# SparkFun_Main_Board_Single_v20.net
KiCad netlist of a schematic drawn in EAGLE
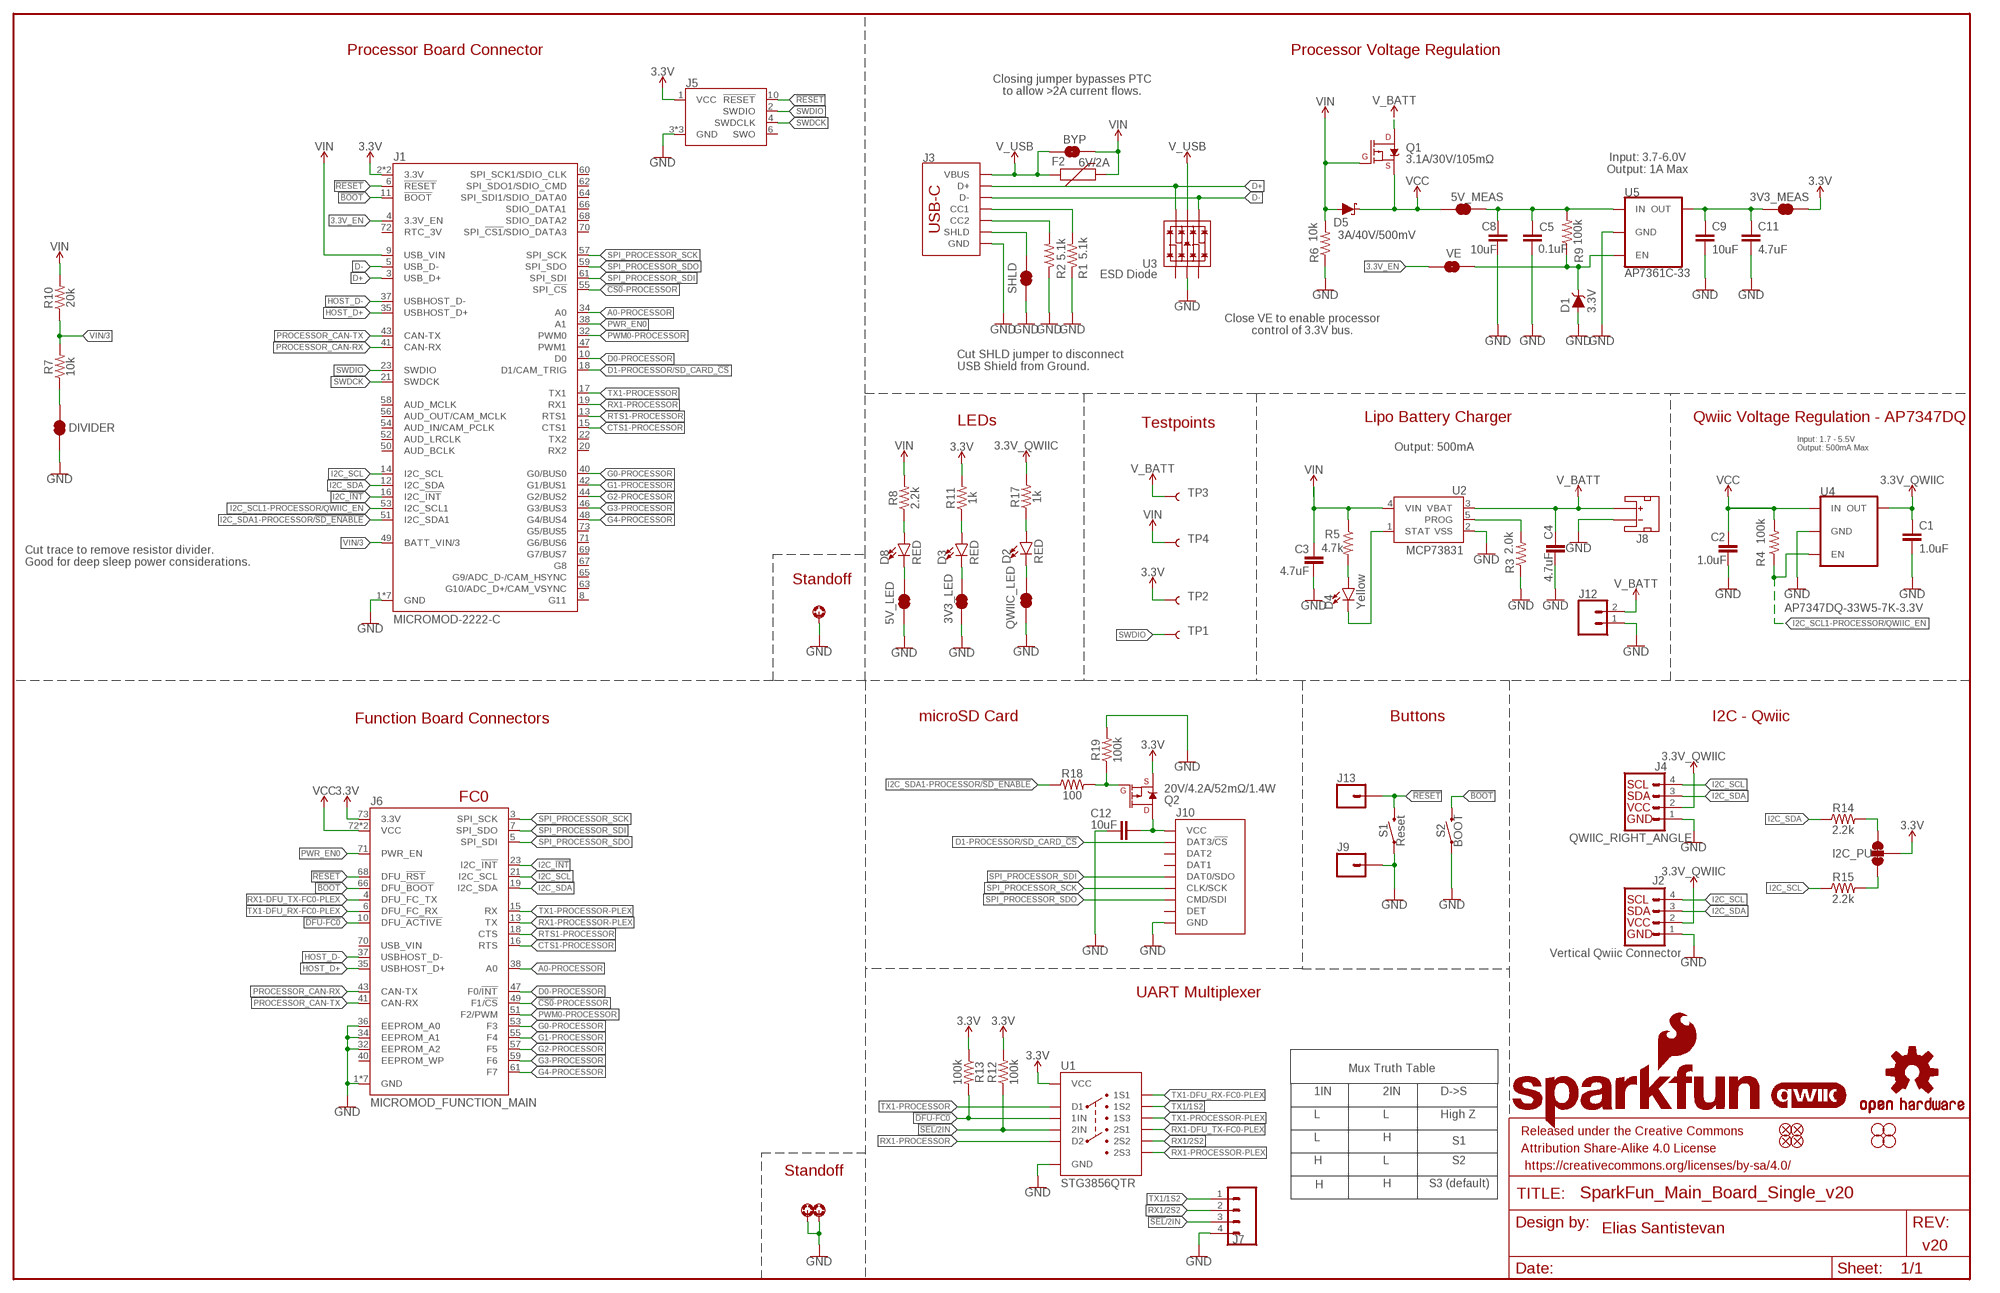
[diagram p0: schematic, sheet 1]

(export (version "E")
  (design (tool "Eeschema 10.0.6"))
  (components
    (comp (ref "3V3_LED")
      (value "JUMPER-SMT_2_NC_TRACE_SILK")
      (footprint "eagle-import:SMT-JUMPER_2_NC_TRACE_SILK")
      (libsource (lib "eagle-import") (part "JUMPER-SMT_2_NC_TRACE_SILK"))
    )
    (comp (ref "3V3_MEAS")
      (value "JUMPER-COMBO_2_NC_TRACE")
      (footprint "eagle-import:COMBO-JUMPER_2_NC_TRACE")
      (libsource (lib "eagle-import") (part "JUMPER-COMBO_2_NC_TRACE"))
    )
    (comp (ref "5V_LED")
      (value "JUMPER-SMT_2_NC_TRACE_SILK")
      (footprint "eagle-import:SMT-JUMPER_2_NC_TRACE_SILK")
      (libsource (lib "eagle-import") (part "JUMPER-SMT_2_NC_TRACE_SILK"))
    )
    (comp (ref "5V_MEAS")
      (value "JUMPER-COMBO_2_NC_TRACE")
      (footprint "eagle-import:COMBO-JUMPER_2_NC_TRACE")
      (libsource (lib "eagle-import") (part "JUMPER-COMBO_2_NC_TRACE"))
    )
    (comp (ref "BYP")
      (value "JUMPER-SMT_2_NO_SILK")
      (footprint "eagle-import:SMT-JUMPER_2_NO_SILK")
      (libsource (lib "eagle-import") (part "JUMPER-SMT_2_NO_SILK"))
    )
    (comp (ref "C1")
      (value "1.0uF")
      (footprint "eagle-import:0603")
      (libsource (lib "eagle-import") (part "1.0UF-0603-16V-10%"))
    )
    (comp (ref "C2")
      (value "1.0uF")
      (footprint "eagle-import:0603")
      (libsource (lib "eagle-import") (part "1.0UF-0603-16V-10%"))
    )
    (comp (ref "C3")
      (value "4.7uF")
      (footprint "eagle-import:0603")
      (libsource (lib "eagle-import") (part "4.7UF-0603-6.3V-(10%)"))
    )
    (comp (ref "C4")
      (value "4.7uF")
      (footprint "eagle-import:0603")
      (libsource (lib "eagle-import") (part "4.7UF-0603-35V-(20%)"))
    )
    (comp (ref "C5")
      (value "0.1uF")
      (footprint "eagle-import:0603")
      (libsource (lib "eagle-import") (part "0.1UF-0603-25V-(+80/-20%)"))
    )
    (comp (ref "C8")
      (value "10uF")
      (footprint "eagle-import:0805")
      (libsource (lib "eagle-import") (part "10UF-0805-10V-10%"))
    )
    (comp (ref "C9")
      (value "10uF")
      (footprint "eagle-import:0603")
      (libsource (lib "eagle-import") (part "10UF-0603-6.3V-20%"))
    )
    (comp (ref "C11")
      (value "4.7uF")
      (footprint "eagle-import:0603")
      (libsource (lib "eagle-import") (part "4.7UF-0603-6.3V-(10%)"))
    )
    (comp (ref "C12")
      (value "10uF")
      (footprint "eagle-import:0603")
      (libsource (lib "eagle-import") (part "10UF-0603-6.3V-20%"))
    )
    (comp (ref "D1")
      (value "3.3V")
      (footprint "eagle-import:SOD-323")
      (libsource (lib "eagle-import") (part "DIODE-ZENER-MM3Z3V3T1G"))
    )
    (comp (ref "D2")
      (value "RED")
      (footprint "eagle-import:LED-0603")
      (libsource (lib "eagle-import") (part "LED-RED0603"))
    )
    (comp (ref "D3")
      (value "RED")
      (footprint "eagle-import:LED-0603")
      (libsource (lib "eagle-import") (part "LED-RED0603"))
    )
    (comp (ref "D4")
      (value "Yellow")
      (footprint "eagle-import:LED-0603")
      (libsource (lib "eagle-import") (part "LED-YELLOW0603"))
    )
    (comp (ref "D5")
      (value "3A/40V/500mV")
      (footprint "eagle-import:SMA-DIODE")
      (libsource (lib "eagle-import") (part "DIODE-SCHOTTKY-B340A"))
    )
    (comp (ref "D8")
      (value "RED")
      (footprint "eagle-import:LED-0603")
      (libsource (lib "eagle-import") (part "LED-RED0603"))
    )
    (comp (ref "DIVIDER")
      (value "JUMPER-SMT_2_NC_TRACE_SILK")
      (footprint "eagle-import:SMT-JUMPER_2_NC_TRACE_SILK")
      (libsource (lib "eagle-import") (part "JUMPER-SMT_2_NC_TRACE_SILK"))
    )
    (comp (ref "F2")
      (value "6V/2A")
      (footprint "eagle-import:1210")
      (libsource (lib "eagle-import") (part "PPTC_6V2A"))
    )
    (comp (ref "FD1")
      (value "FIDUCIAL1X2")
      (footprint "eagle-import:FIDUCIAL-1X2")
      (libsource (lib "eagle-import") (part "FIDUCIAL1X2"))
    )
    (comp (ref "FD2")
      (value "FIDUCIAL1X2")
      (footprint "eagle-import:FIDUCIAL-1X2")
      (libsource (lib "eagle-import") (part "FIDUCIAL1X2"))
    )
    (comp (ref "FD3")
      (value "FIDUCIAL1X2")
      (footprint "eagle-import:FIDUCIAL-1X2")
      (libsource (lib "eagle-import") (part "FIDUCIAL1X2"))
    )
    (comp (ref "FD4")
      (value "FIDUCIAL1X2")
      (footprint "eagle-import:FIDUCIAL-1X2")
      (libsource (lib "eagle-import") (part "FIDUCIAL1X2"))
    )
    (comp (ref "FRAME1")
      (value "FRAME-LEDGER")
      (footprint "eagle-import:CREATIVE_COMMONS")
      (libsource (lib "eagle-import") (part "FRAME-LEDGER"))
    )
    (comp (ref "H2")
      (value "STAND-OFF-REFLOW-M2.5_2.5MM_TALL")
      (footprint "eagle-import:STAND-OFF-REFLOW-M2.5")
      (libsource (lib "eagle-import") (part "STAND-OFF-REFLOW-M2.5_2.5MM_TALL"))
    )
    (comp (ref "H4")
      (value "STAND-OFF-REFLOW-M2.5_2.5MM_TALL")
      (footprint "eagle-import:STAND-OFF-REFLOW-M2.5")
      (libsource (lib "eagle-import") (part "STAND-OFF-REFLOW-M2.5_2.5MM_TALL"))
    )
    (comp (ref "H8")
      (value "STAND-OFF-REFLOW-M2.5_2.5MM_TALL")
      (footprint "eagle-import:STAND-OFF-REFLOW-M2.5")
      (libsource (lib "eagle-import") (part "STAND-OFF-REFLOW-M2.5_2.5MM_TALL"))
    )
    (comp (ref "H14")
      (value "STAND-OFFTIGHT")
      (footprint "eagle-import:STAND-OFF-TIGHT")
      (libsource (lib "eagle-import") (part "STAND-OFFTIGHT"))
    )
    (comp (ref "H15")
      (value "STAND-OFFTIGHT")
      (footprint "eagle-import:STAND-OFF-TIGHT")
      (libsource (lib "eagle-import") (part "STAND-OFFTIGHT"))
    )
    (comp (ref "H16")
      (value "STAND-OFFTIGHT")
      (footprint "eagle-import:STAND-OFF-TIGHT")
      (libsource (lib "eagle-import") (part "STAND-OFFTIGHT"))
    )
    (comp (ref "H17")
      (value "STAND-OFFTIGHT")
      (footprint "eagle-import:STAND-OFF-TIGHT")
      (libsource (lib "eagle-import") (part "STAND-OFFTIGHT"))
    )
    (comp (ref "I2C_PU")
      (value "JUMPER-SMT_3_2-NC_TRACE_SILK")
      (footprint "eagle-import:SMT-JUMPER_3_2-NC_TRACE_SILK")
      (libsource (lib "eagle-import") (part "JUMPER-SMT_3_2-NC_TRACE_SILK"))
    )
    (comp (ref "J1")
      (value "MICROMOD-2222-C")
      (footprint "eagle-import:M.2-CONNECTOR-E")
      (libsource (lib "eagle-import") (part "MICROMOD-2222-C"))
    )
    (comp (ref "J2")
      (value "Vertical Qwiic Connector")
      (footprint "eagle-import:JST04_1MM_VERT")
      (libsource (lib "eagle-import") (part "QWIIC_CONNECTOR"))
    )
    (comp (ref "J3")
      (value "USB_C_2-LAYER_PADS")
      (footprint "eagle-import:USB-C-16P-2LAYER-PADS")
      (libsource (lib "eagle-import") (part "USB_C_2-LAYER_PADS"))
    )
    (comp (ref "J4")
      (value "QWIIC_RIGHT_ANGLE")
      (footprint "eagle-import:JST04_1MM_RA")
      (libsource (lib "eagle-import") (part "QWIIC_CONNECTORJS-1MM"))
    )
    (comp (ref "J5")
      (value "CORTEX_JTAG_DEBUG_MINIMUM_PTH")
      (footprint "eagle-import:2X5-PTH-1.27MM")
      (libsource (lib "eagle-import") (part "CORTEX_JTAG_DEBUG_MINIMUM_PTH"))
    )
    (comp (ref "J6")
      (value "MICROMOD_FUNCTION_MAIN")
      (footprint "eagle-import:M.2-CONNECTOR-E-FUNCTION-STANDARD")
      (libsource (lib "eagle-import") (part "MICROMOD_FUNCTION_MAIN"))
    )
    (comp (ref "J7")
      (value "CONN_041X04_NO_SILK")
      (footprint "eagle-import:1X04_NO_SILK")
      (libsource (lib "eagle-import") (part "CONN_041X04_NO_SILK"))
    )
    (comp (ref "J8")
      (value "JST_2MM_MALE")
      (footprint "eagle-import:JST-2-SMD")
      (libsource (lib "eagle-import") (part "JST_2MM_MALE"))
    )
    (comp (ref "J9")
      (value "CONN_01PTH_NO_SILK_YES_STOP")
      (footprint "eagle-import:1X01_NO_SILK")
      (libsource (lib "eagle-import") (part "CONN_01PTH_NO_SILK_YES_STOP"))
    )
    (comp (ref "J10")
      (value "MICRO-SD-PUSH-PUSH-EXT-PIN")
      (footprint "eagle-import:MICROSD-EXTERNALPIN")
      (libsource (lib "eagle-import") (part "MICRO-SD-PUSH-PUSH-EXT-PIN"))
    )
    (comp (ref "J12")
      (value "CONN_021X02_NO_SILK")
      (footprint "eagle-import:1X02_NO_SILK")
      (libsource (lib "eagle-import") (part "CONN_021X02_NO_SILK"))
    )
    (comp (ref "J13")
      (value "CONN_01PTH_NO_SILK_YES_STOP")
      (footprint "eagle-import:1X01_NO_SILK")
      (libsource (lib "eagle-import") (part "CONN_01PTH_NO_SILK_YES_STOP"))
    )
    (comp (ref "LOGO1")
      (value "QWIIC_LOGO_8MM")
      (footprint "eagle-import:QWIIC_8MM")
      (libsource (lib "eagle-import") (part "QWIIC_LOGO_8MM"))
    )
    (comp (ref "LOGO2")
      (value "SFE_LOGO_NAME_FLAME.3_INCH")
      (footprint "eagle-import:SFE_LOGO_NAME_FLAME_.3")
      (libsource (lib "eagle-import") (part "SFE_LOGO_NAME_FLAME.3_INCH"))
    )
    (comp (ref "LOGO3")
      (value "OSHW-LOGOL")
      (footprint "eagle-import:OSHW-LOGO-L")
      (libsource (lib "eagle-import") (part "OSHW-LOGOL"))
    )
    (comp (ref "Q1")
      (value "3.1A/30V/105mΩ")
      (footprint "eagle-import:SOT23-3")
      (libsource (lib "eagle-import") (part "MOSFET_PCH-DMG2307L"))
    )
    (comp (ref "Q2")
      (value "20V/4.2A/52mΩ/1.4W")
      (footprint "eagle-import:SOT23-3")
      (libsource (lib "eagle-import") (part "MOSFET_PCH-DMG2305UX-7"))
    )
    (comp (ref "QWIIC_LED")
      (value "JUMPER-SMT_2_NC_TRACE_SILK")
      (footprint "eagle-import:SMT-JUMPER_2_NC_TRACE_SILK")
      (libsource (lib "eagle-import") (part "JUMPER-SMT_2_NC_TRACE_SILK"))
    )
    (comp (ref "R1")
      (value "5.1k")
      (footprint "eagle-import:0603")
      (libsource (lib "eagle-import") (part "5.1KOHM5.1KOHM-0603-1/10W-1%"))
    )
    (comp (ref "R2")
      (value "5.1k")
      (footprint "eagle-import:0603")
      (libsource (lib "eagle-import") (part "5.1KOHM5.1KOHM-0603-1/10W-1%"))
    )
    (comp (ref "R3")
      (value "2.0k")
      (footprint "eagle-import:0603")
      (libsource (lib "eagle-import") (part "2.0KOHM-0603-1/10W-5%"))
    )
    (comp (ref "R4")
      (value "100k")
      (footprint "eagle-import:0603")
      (libsource (lib "eagle-import") (part "100KOHM-0603-1/10W-1%"))
    )
    (comp (ref "R5")
      (value "4.7k")
      (footprint "eagle-import:0603")
      (libsource (lib "eagle-import") (part "4.7KOHM-0603-1/10W-1%"))
    )
    (comp (ref "R6")
      (value "10k")
      (footprint "eagle-import:0603")
      (libsource (lib "eagle-import") (part "10KOHM-0603-1/10W-1%"))
    )
    (comp (ref "R7")
      (value "10k")
      (footprint "eagle-import:0603")
      (libsource (lib "eagle-import") (part "10KOHM-0603-1/10W-1%"))
    )
    (comp (ref "R8")
      (value "2.2k")
      (footprint "eagle-import:0603")
      (libsource (lib "eagle-import") (part "2.2KOHM-0603-1/10W-1%"))
    )
    (comp (ref "R9")
      (value "100k")
      (footprint "eagle-import:0603")
      (libsource (lib "eagle-import") (part "100KOHM-0603-1/10W-1%"))
    )
    (comp (ref "R10")
      (value "20k")
      (footprint "eagle-import:0603")
      (libsource (lib "eagle-import") (part "20KOHM-0603-1/10W-1%"))
    )
    (comp (ref "R11")
      (value "1k")
      (footprint "eagle-import:0603")
      (libsource (lib "eagle-import") (part "1KOHM-0603-1/10W-1%"))
    )
    (comp (ref "R12")
      (value "100k")
      (footprint "eagle-import:0603")
      (libsource (lib "eagle-import") (part "100KOHM-0603-1/10W-1%"))
    )
    (comp (ref "R13")
      (value "100k")
      (footprint "eagle-import:0603")
      (libsource (lib "eagle-import") (part "100KOHM-0603-1/10W-1%"))
    )
    (comp (ref "R14")
      (value "2.2k")
      (footprint "eagle-import:0603")
      (libsource (lib "eagle-import") (part "2.2KOHM-0603-1/10W-1%"))
    )
    (comp (ref "R15")
      (value "2.2k")
      (footprint "eagle-import:0603")
      (libsource (lib "eagle-import") (part "2.2KOHM-0603-1/10W-1%"))
    )
    (comp (ref "R17")
      (value "1k")
      (footprint "eagle-import:0603")
      (libsource (lib "eagle-import") (part "1KOHM-0603-1/10W-1%"))
    )
    (comp (ref "R18")
      (value "100")
      (footprint "eagle-import:0603")
      (libsource (lib "eagle-import") (part "100OHM-0603-1/10W-1%"))
    )
    (comp (ref "R19")
      (value "100k")
      (footprint "eagle-import:0603")
      (libsource (lib "eagle-import") (part "100KOHM-0603-1/10W-1%"))
    )
    (comp (ref "S1")
      (value "Reset")
      (footprint "eagle-import:TACTILE_SWITCH_SMD_5.2MM")
      (libsource (lib "eagle-import") (part "MOMENTARY-SWITCH-SPST-SMD-5.2-TALL-REDUNDANT"))
    )
    (comp (ref "S2")
      (value "BOOT")
      (footprint "eagle-import:TACTILE_SWITCH_SMD_5.2MM")
      (libsource (lib "eagle-import") (part "MOMENTARY-SWITCH-SPST-SMD-5.2-TALL-REDUNDANT"))
    )
    (comp (ref "SHLD")
      (value "JUMPER-SMT_2_NC_TRACE_SILK")
      (footprint "eagle-import:SMT-JUMPER_2_NC_TRACE_SILK")
      (libsource (lib "eagle-import") (part "JUMPER-SMT_2_NC_TRACE_SILK"))
    )
    (comp (ref "TP1")
      (value "TEST-POINT3X5")
      (footprint "eagle-import:PAD.03X.05")
      (libsource (lib "eagle-import") (part "TEST-POINT3X5"))
    )
    (comp (ref "TP2")
      (value "TEST-POINT3X5")
      (footprint "eagle-import:PAD.03X.05")
      (libsource (lib "eagle-import") (part "TEST-POINT3X5"))
    )
    (comp (ref "TP3")
      (value "TEST-POINT3X5")
      (footprint "eagle-import:PAD.03X.05")
      (libsource (lib "eagle-import") (part "TEST-POINT3X5"))
    )
    (comp (ref "TP4")
      (value "TEST-POINT3X5")
      (footprint "eagle-import:PAD.03X.05")
      (libsource (lib "eagle-import") (part "TEST-POINT3X5"))
    )
    (comp (ref "U1")
      (value "STG3856QTR")
      (footprint "eagle-import:STG3856")
      (libsource (lib "eagle-import") (part "STG3856QTR"))
    )
    (comp (ref "U2")
      (value "MCP73831")
      (footprint "eagle-import:SOT23-5")
      (libsource (lib "eagle-import") (part "MCP73831"))
    )
    (comp (ref "U3")
      (value "ESD Diode")
      (footprint "eagle-import:SOT-23-6")
      (libsource (lib "eagle-import") (part "TVS_DIODE_ARRAYSMD"))
    )
    (comp (ref "U4")
      (value "AP7347DQ-33W5-7K-3.3V")
      (footprint "eagle-import:SOT25")
      (libsource (lib "eagle-import") (part "AP7347DQ-33W5-7K-3.3V"))
    )
    (comp (ref "U5")
      (value "AP7361C-33")
      (footprint "eagle-import:UDFN-8")
      (libsource (lib "eagle-import") (part "AP7361C-33FGEUDFN-8"))
    )
    (comp (ref "VE")
      (value "JUMPER-SMT_2_NO_SILK")
      (footprint "eagle-import:SMT-JUMPER_2_NO_SILK")
      (libsource (lib "eagle-import") (part "JUMPER-SMT_2_NO_SILK"))
    )
  )
  (nets
    (net (code "1") (name "/D1-PROCESSOR{slash}SD_CARD_~{CS}") (class "Default")
      (node (ref "J1") (pin "18") (pinfunction "D1/CAM_TRIG_18") (pintype "bidirectional"))
      (node (ref "J10") (pin "2") (pinfunction "DAT3/~{CS}_2") (pintype "bidirectional"))
    )
    (net (code "2") (name "/I2C_SDA1-PROCESSOR{slash}~{SD_ENABLE}") (class "Default")
      (node (ref "J1") (pin "51") (pinfunction "I2C_SDA1_51") (pintype "bidirectional"))
      (node (ref "R18") (pin "1") (pinfunction "1_1") (pintype "passive"))
    )
    (net (code "3") (name "/I2C_~{INT}") (class "Default")
      (node (ref "J1") (pin "16") (pinfunction "I2C_~{INT}_16") (pintype "bidirectional"))
      (node (ref "J6") (pin "23") (pinfunction "I2C_~{INT}_23") (pintype "bidirectional"))
    )
    (net (code "4") (name "/~{BOOT}") (class "Default")
      (node (ref "J1") (pin "11") (pinfunction "~{BOOT}_11") (pintype "bidirectional"))
      (node (ref "J6") (pin "66") (pinfunction "DFU_~{BOOT}_66") (pintype "bidirectional"))
      (node (ref "S2") (pin "3") (pinfunction "2_3") (pintype "passive"))
      (node (ref "S2") (pin "4") (pinfunction "2_4") (pintype "passive"))
    )
    (net (code "5") (name "/~{CS0}-PROCESSOR") (class "Default")
      (node (ref "J1") (pin "55") (pinfunction "SPI_~{CS}_55") (pintype "bidirectional"))
      (node (ref "J6") (pin "49") (pinfunction "F1/~{CS}_49") (pintype "bidirectional"))
    )
    (net (code "6") (name "/~{DFU-FC0}") (class "Default")
      (node (ref "J6") (pin "10") (pinfunction "DFU_~{ACTIVE}_10") (pintype "bidirectional"))
      (node (ref "R13") (pin "2") (pinfunction "2_2") (pintype "passive"))
      (node (ref "U1") (pin "P12") (pinfunction "1IN_P12") (pintype "bidirectional"))
    )
    (net (code "7") (name "/~{RESET}") (class "Default")
      (node (ref "J1") (pin "6") (pinfunction "~{RESET}_6") (pintype "bidirectional"))
      (node (ref "J13") (pin "1") (pinfunction "1_1") (pintype "passive"))
      (node (ref "J5") (pin "10") (pinfunction "~{RESET}_10") (pintype "bidirectional"))
      (node (ref "J6") (pin "68") (pinfunction "DFU_~{RST}_68") (pintype "bidirectional"))
      (node (ref "S1") (pin "3") (pinfunction "2_3") (pintype "passive"))
      (node (ref "S1") (pin "4") (pinfunction "2_4") (pintype "passive"))
    )
    (net (code "8") (name "/~{SEL}{slash}2IN") (class "Default")
      (node (ref "J7") (pin "3") (pinfunction "3_3") (pintype "passive"))
      (node (ref "R12") (pin "1") (pinfunction "1_1") (pintype "passive"))
      (node (ref "U1") (pin "P10") (pinfunction "2IN_P10") (pintype "bidirectional"))
    )
    (net (code "9") (name "3.3V") (class "Default")
      (node (ref "3V3_MEAS") (pin "2") (pinfunction "2_2") (pintype "passive"))
      (node (ref "3V3_MEAS") (pin "4") (pinfunction "2_4") (pintype "passive"))
      (node (ref "I2C_PU") (pin "2") (pinfunction "2_2") (pintype "passive"))
      (node (ref "J1") (pin "2") (pinfunction "3.3V_2") (pintype "bidirectional"))
      (node (ref "J1") (pin "74") (pinfunction "3.3V_74") (pintype "bidirectional"))
      (node (ref "J5") (pin "1") (pinfunction "VCC_1") (pintype "bidirectional"))
      (node (ref "J6") (pin "73") (pinfunction "3.3V_73") (pintype "bidirectional"))
      (node (ref "Q2") (pin "2") (pinfunction "S_2") (pintype "bidirectional"))
      (node (ref "R11") (pin "2") (pinfunction "2_2") (pintype "passive"))
      (node (ref "R12") (pin "2") (pinfunction "2_2") (pintype "passive"))
      (node (ref "R13") (pin "1") (pinfunction "1_1") (pintype "passive"))
      (node (ref "TP2") (pin "1") (pinfunction "1_1") (pintype "bidirectional"))
      (node (ref "U1") (pin "P11") (pinfunction "VCC_P11") (pintype "power_in"))
    )
    (net (code "10") (name "3.3V_EN") (class "Default")
      (node (ref "J1") (pin "4") (pinfunction "3.3V_EN_4") (pintype "bidirectional"))
      (node (ref "VE") (pin "1") (pinfunction "1_1") (pintype "passive"))
    )
    (net (code "11") (name "3.3V_QWIIC") (class "Default")
      (node (ref "C1") (pin "1") (pinfunction "1_1") (pintype "passive"))
      (node (ref "J2") (pin "2") (pinfunction "2_2") (pintype "power_in"))
      (node (ref "J4") (pin "2") (pinfunction "2_2") (pintype "power_in"))
      (node (ref "R17") (pin "2") (pinfunction "2_2") (pintype "passive"))
      (node (ref "U4") (pin "5") (pinfunction "OUT_5") (pintype "passive"))
    )
    (net (code "12") (name "A0-PROCESSOR") (class "Default")
      (node (ref "J1") (pin "34") (pinfunction "A0_34") (pintype "bidirectional"))
      (node (ref "J6") (pin "38") (pinfunction "A0_38") (pintype "bidirectional"))
    )
    (net (code "13") (name "CTS1-PROCESSOR") (class "Default")
      (node (ref "J1") (pin "15") (pinfunction "CTS1_15") (pintype "bidirectional"))
      (node (ref "J6") (pin "16") (pinfunction "RTS_16") (pintype "bidirectional"))
    )
    (net (code "14") (name "D+") (class "Default")
      (node (ref "J1") (pin "3") (pinfunction "USB_D+_3") (pintype "bidirectional"))
      (node (ref "J3") (pin "A6") (pinfunction "D+_A6") (pintype "bidirectional"))
      (node (ref "J3") (pin "B6") (pinfunction "D+_B6") (pintype "bidirectional"))
      (node (ref "U3") (pin "6") (pinfunction "IO4_6") (pintype "bidirectional"))
    )
    (net (code "15") (name "D-") (class "Default")
      (node (ref "J1") (pin "5") (pinfunction "USB_D-_5") (pintype "bidirectional"))
      (node (ref "J3") (pin "A7") (pinfunction "D-_A7") (pintype "bidirectional"))
      (node (ref "J3") (pin "B7") (pinfunction "D-_B7") (pintype "bidirectional"))
      (node (ref "U3") (pin "4") (pinfunction "IO3_4") (pintype "bidirectional"))
    )
    (net (code "16") (name "D0-PROCESSOR") (class "Default")
      (node (ref "J1") (pin "10") (pinfunction "D0_10") (pintype "bidirectional"))
      (node (ref "J6") (pin "47") (pinfunction "F0/~{INT}_47") (pintype "bidirectional"))
    )
    (net (code "17") (name "G0-PROCESSOR") (class "Default")
      (node (ref "J1") (pin "40") (pinfunction "G0/BUS0_40") (pintype "bidirectional"))
      (node (ref "J6") (pin "53") (pinfunction "F3_53") (pintype "bidirectional"))
    )
    (net (code "18") (name "G1-PROCESSOR") (class "Default")
      (node (ref "J1") (pin "42") (pinfunction "G1/BUS1_42") (pintype "bidirectional"))
      (node (ref "J6") (pin "55") (pinfunction "F4_55") (pintype "bidirectional"))
    )
    (net (code "19") (name "G2-PROCESSOR") (class "Default")
      (node (ref "J1") (pin "44") (pinfunction "G2/BUS2_44") (pintype "bidirectional"))
      (node (ref "J6") (pin "57") (pinfunction "F5_57") (pintype "bidirectional"))
    )
    (net (code "20") (name "G3-PROCESSOR") (class "Default")
      (node (ref "J1") (pin "46") (pinfunction "G3/BUS3_46") (pintype "bidirectional"))
      (node (ref "J6") (pin "59") (pinfunction "F6_59") (pintype "bidirectional"))
    )
    (net (code "21") (name "G4-PROCESSOR") (class "Default")
      (node (ref "J1") (pin "48") (pinfunction "G4/BUS4_48") (pintype "bidirectional"))
      (node (ref "J6") (pin "61") (pinfunction "F7_61") (pintype "bidirectional"))
    )
    (net (code "22") (name "GND") (class "Default")
      (node (ref "3V3_LED") (pin "1") (pinfunction "1_1") (pintype "passive"))
      (node (ref "5V_LED") (pin "1") (pinfunction "1_1") (pintype "passive"))
      (node (ref "C1") (pin "2") (pinfunction "2_2") (pintype "passive"))
      (node (ref "C11") (pin "2") (pinfunction "2_2") (pintype "passive"))
      (node (ref "C12") (pin "2") (pinfunction "2_2") (pintype "passive"))
      (node (ref "C2") (pin "2") (pinfunction "2_2") (pintype "passive"))
      (node (ref "C3") (pin "2") (pinfunction "2_2") (pintype "passive"))
      (node (ref "C4") (pin "2") (pinfunction "2_2") (pintype "passive"))
      (node (ref "C5") (pin "2") (pinfunction "2_2") (pintype "passive"))
      (node (ref "C8") (pin "2") (pinfunction "2_2") (pintype "passive"))
      (node (ref "C9") (pin "2") (pinfunction "2_2") (pintype "passive"))
      (node (ref "D1") (pin "A") (pinfunction "A_A") (pintype "passive"))
      (node (ref "DIVIDER") (pin "1") (pinfunction "1_1") (pintype "passive"))
      (node (ref "H2") (pin "1") (pinfunction "1_1") (pintype "bidirectional"))
      (node (ref "H4") (pin "1") (pinfunction "1_1") (pintype "bidirectional"))
      (node (ref "H8") (pin "1") (pinfunction "1_1") (pintype "bidirectional"))
      (node (ref "J1") (pin "1") (pinfunction "GND_1") (pintype "bidirectional"))
      (node (ref "J1") (pin "33") (pinfunction "GND_33") (pintype "bidirectional"))
      (node (ref "J1") (pin "36") (pinfunction "GND_36") (pintype "bidirectional"))
      (node (ref "J1") (pin "39") (pinfunction "GND_39") (pintype "bidirectional"))
      (node (ref "J1") (pin "45") (pinfunction "GND_45") (pintype "bidirectional"))
      (node (ref "J1") (pin "7") (pinfunction "GND_7") (pintype "bidirectional"))
      (node (ref "J1") (pin "75") (pinfunction "GND_75") (pintype "bidirectional"))
      (node (ref "J10") (pin "10") (pinfunction "GND_10") (pintype "bidirectional"))
      (node (ref "J10") (pin "11") (pinfunction "GND_11") (pintype "bidirectional"))
      (node (ref "J10") (pin "12") (pinfunction "GND_12") (pintype "bidirectional"))
      (node (ref "J10") (pin "13") (pinfunction "GND_13") (pintype "bidirectional"))
      (node (ref "J10") (pin "6") (pinfunction "GND_6") (pintype "bidirectional"))
      (node (ref "J12") (pin "1") (pinfunction "1_1") (pintype "passive"))
      (node (ref "J2") (pin "1") (pinfunction "1_1") (pintype "power_in"))
      (node (ref "J3") (pin "GND") (pinfunction "GND_GND") (pintype "bidirectional"))
      (node (ref "J3") (pin "GND2") (pinfunction "GND_GND2") (pintype "bidirectional"))
      (node (ref "J4") (pin "1") (pinfunction "1_1") (pintype "power_in"))
      (node (ref "J5") (pin "3") (pinfunction "GND_3") (pintype "bidirectional"))
      (node (ref "J5") (pin "5") (pinfunction "GND_5") (pintype "bidirectional"))
      (node (ref "J5") (pin "9") (pinfunction "GND_9") (pintype "bidirectional"))
      (node (ref "J6") (pin "1") (pinfunction "GND_1") (pintype "bidirectional"))
      (node (ref "J6") (pin "2") (pinfunction "GND_2") (pintype "bidirectional"))
      (node (ref "J6") (pin "32") (pinfunction "EEPROM_A2_32") (pintype "bidirectional"))
      (node (ref "J6") (pin "33") (pinfunction "GND_33") (pintype "bidirectional"))
      (node (ref "J6") (pin "34") (pinfunction "EEPROM_A1_34") (pintype "bidirectional"))
      (node (ref "J6") (pin "36") (pinfunction "EEPROM_A0_36") (pintype "bidirectional"))
      (node (ref "J6") (pin "39") (pinfunction "GND_39") (pintype "bidirectional"))
      (node (ref "J6") (pin "45") (pinfunction "GND_45") (pintype "bidirectional"))
      (node (ref "J6") (pin "75") (pinfunction "GND_75") (pintype "bidirectional"))
      (node (ref "J6") (pin "8") (pinfunction "GND_8") (pintype "bidirectional"))
      (node (ref "J7") (pin "4") (pinfunction "4_4") (pintype "passive"))
      (node (ref "J8") (pin "1") (pinfunction "-_1") (pintype "bidirectional"))
      (node (ref "J9") (pin "1") (pinfunction "1_1") (pintype "passive"))
      (node (ref "QWIIC_LED") (pin "1") (pinfunction "1_1") (pintype "passive"))
      (node (ref "R1") (pin "1") (pinfunction "1_1") (pintype "passive"))
      (node (ref "R19") (pin "2") (pinfunction "2_2") (pintype "passive"))
      (node (ref "R2") (pin "1") (pinfunction "1_1") (pintype "passive"))
      (node (ref "R3") (pin "1") (pinfunction "1_1") (pintype "passive"))
      (node (ref "R6") (pin "1") (pinfunction "1_1") (pintype "passive"))
      (node (ref "S1") (pin "1") (pinfunction "1_1") (pintype "passive"))
      (node (ref "S1") (pin "2") (pinfunction "1_2") (pintype "passive"))
      (node (ref "S2") (pin "1") (pinfunction "1_1") (pintype "passive"))
      (node (ref "S2") (pin "2") (pinfunction "1_2") (pintype "passive"))
      (node (ref "SHLD") (pin "1") (pinfunction "1_1") (pintype "passive"))
      (node (ref "U1") (pin "P5") (pinfunction "GND_P5") (pintype "power_in"))
      (node (ref "U2") (pin "2") (pinfunction "VSS_2") (pintype "power_in"))
      (node (ref "U3") (pin "2") (pinfunction "VSS_2") (pintype "bidirectional"))
      (node (ref "U4") (pin "2") (pinfunction "GND_2") (pintype "input"))
      (node (ref "U5") (pin "4") (pinfunction "GND_4") (pintype "input"))
      (node (ref "U5") (pin "EP") (pinfunction "GND_EP") (pintype "input"))
    )
    (net (code "23") (name "HOST_D+") (class "Default")
      (node (ref "J1") (pin "35") (pinfunction "USBHOST_D+_35") (pintype "bidirectional"))
      (node (ref "J6") (pin "35") (pinfunction "USBHOST_D+_35") (pintype "bidirectional"))
    )
    (net (code "24") (name "HOST_D-") (class "Default")
      (node (ref "J1") (pin "37") (pinfunction "USBHOST_D-_37") (pintype "bidirectional"))
      (node (ref "J6") (pin "37") (pinfunction "USBHOST_D-_37") (pintype "bidirectional"))
    )
    (net (code "25") (name "I2C_SCL") (class "Default")
      (node (ref "J1") (pin "14") (pinfunction "I2C_SCL_14") (pintype "bidirectional"))
      (node (ref "J2") (pin "4") (pinfunction "4_4") (pintype "passive"))
      (node (ref "J4") (pin "4") (pinfunction "4_4") (pintype "passive"))
      (node (ref "J6") (pin "21") (pinfunction "I2C_SCL_21") (pintype "bidirectional"))
      (node (ref "R15") (pin "1") (pinfunction "1_1") (pintype "passive"))
    )
    (net (code "26") (name "I2C_SCL1-PROCESSOR{slash}QWIIC_EN") (class "Default")
      (node (ref "J1") (pin "53") (pinfunction "I2C_SCL1_53") (pintype "bidirectional"))
      (node (ref "R4") (pin "1") (pinfunction "1_1") (pintype "passive"))
      (node (ref "U4") (pin "3") (pinfunction "EN_3") (pintype "input"))
    )
    (net (code "27") (name "I2C_SDA") (class "Default")
      (node (ref "J1") (pin "12") (pinfunction "I2C_SDA_12") (pintype "bidirectional"))
      (node (ref "J2") (pin "3") (pinfunction "3_3") (pintype "passive"))
      (node (ref "J4") (pin "3") (pinfunction "3_3") (pintype "passive"))
      (node (ref "J6") (pin "19") (pinfunction "I2C_SDA_19") (pintype "bidirectional"))
      (node (ref "R14") (pin "1") (pinfunction "1_1") (pintype "passive"))
    )
    (net (code "28") (name "Net-(3V3_LED-Pad2)") (class "Default")
      (node (ref "3V3_LED") (pin "2") (pinfunction "2_2") (pintype "passive"))
      (node (ref "D3") (pin "C") (pinfunction "C_C") (pintype "passive"))
    )
    (net (code "29") (name "Net-(5V_LED-Pad2)") (class "Default")
      (node (ref "5V_LED") (pin "2") (pinfunction "2_2") (pintype "passive"))
      (node (ref "D8") (pin "C") (pinfunction "C_C") (pintype "passive"))
    )
    (net (code "30") (name "Net-(D2-PadA)") (class "Default")
      (node (ref "D2") (pin "A") (pinfunction "A_A") (pintype "passive"))
      (node (ref "R17") (pin "1") (pinfunction "1_1") (pintype "passive"))
    )
    (net (code "31") (name "Net-(D2-PadC)") (class "Default")
      (node (ref "D2") (pin "C") (pinfunction "C_C") (pintype "passive"))
      (node (ref "QWIIC_LED") (pin "2") (pinfunction "2_2") (pintype "passive"))
    )
    (net (code "32") (name "Net-(D3-PadA)") (class "Default")
      (node (ref "D3") (pin "A") (pinfunction "A_A") (pintype "passive"))
      (node (ref "R11") (pin "1") (pinfunction "1_1") (pintype "passive"))
    )
    (net (code "33") (name "Net-(D4-PadA)") (class "Default")
      (node (ref "D4") (pin "A") (pinfunction "A_A") (pintype "passive"))
      (node (ref "R5") (pin "2") (pinfunction "2_2") (pintype "passive"))
    )
    (net (code "34") (name "Net-(D8-PadA)") (class "Default")
      (node (ref "D8") (pin "A") (pinfunction "A_A") (pintype "passive"))
      (node (ref "R8") (pin "1") (pinfunction "1_1") (pintype "passive"))
    )
    (net (code "35") (name "Net-(DIVIDER-Pad2)") (class "Default")
      (node (ref "DIVIDER") (pin "2") (pinfunction "2_2") (pintype "passive"))
      (node (ref "R7") (pin "1") (pinfunction "1_1") (pintype "passive"))
    )
    (net (code "36") (name "Net-(I2C_PU-Pad1)") (class "Default")
      (node (ref "I2C_PU") (pin "1") (pinfunction "1_1") (pintype "passive"))
      (node (ref "R15") (pin "2") (pinfunction "2_2") (pintype "passive"))
    )
    (net (code "37") (name "Net-(I2C_PU-Pad3)") (class "Default")
      (node (ref "I2C_PU") (pin "3") (pinfunction "3_3") (pintype "passive"))
      (node (ref "R14") (pin "2") (pinfunction "2_2") (pintype "passive"))
    )
    (net (code "38") (name "Net-(J3-CC1)") (class "Default")
      (node (ref "J3") (pin "A5") (pinfunction "CC1_A5") (pintype "bidirectional"))
      (node (ref "R1") (pin "2") (pinfunction "2_2") (pintype "passive"))
    )
    (net (code "39") (name "Net-(J3-CC2)") (class "Default")
      (node (ref "J3") (pin "B5") (pinfunction "CC2_B5") (pintype "bidirectional"))
      (node (ref "R2") (pin "2") (pinfunction "2_2") (pintype "passive"))
    )
    (net (code "40") (name "Net-(J3-SHLD-PadSHLD1)") (class "Default")
      (node (ref "J3") (pin "SHLD1") (pinfunction "SHLD_SHLD1") (pintype "bidirectional"))
      (node (ref "J3") (pin "SHLD2") (pinfunction "SHLD_SHLD2") (pintype "bidirectional"))
      (node (ref "J3") (pin "SHLD3") (pinfunction "SHLD_SHLD3") (pintype "bidirectional"))
      (node (ref "J3") (pin "SHLD4") (pinfunction "SHLD_SHLD4") (pintype "bidirectional"))
      (node (ref "SHLD") (pin "2") (pinfunction "2_2") (pintype "passive"))
    )
    (net (code "41") (name "Net-(J10-VCC)") (class "Default")
      (node (ref "C12") (pin "1") (pinfunction "1_1") (pintype "passive"))
      (node (ref "J10") (pin "4") (pinfunction "VCC_4") (pintype "bidirectional"))
      (node (ref "Q2") (pin "3") (pinfunction "D_3") (pintype "bidirectional"))
    )
    (net (code "42") (name "Net-(Q2-G)") (class "Default")
      (node (ref "Q2") (pin "1") (pinfunction "G_1") (pintype "bidirectional"))
      (node (ref "R18") (pin "2") (pinfunction "2_2") (pintype "passive"))
      (node (ref "R19") (pin "1") (pinfunction "1_1") (pintype "passive"))
    )
    (net (code "43") (name "Net-(U2-PROG)") (class "Default")
      (node (ref "R3") (pin "2") (pinfunction "2_2") (pintype "passive"))
      (node (ref "U2") (pin "5") (pinfunction "PROG_5") (pintype "input"))
    )
    (net (code "44") (name "Net-(U2-STAT)") (class "Default")
      (node (ref "D4") (pin "C") (pinfunction "C_C") (pintype "passive"))
      (node (ref "U2") (pin "1") (pinfunction "STAT_1") (pintype "output"))
    )
    (net (code "45") (name "Net-(U5-EN)") (class "Default")
      (node (ref "D1") (pin "C") (pinfunction "C_C") (pintype "passive"))
      (node (ref "R9") (pin "1") (pinfunction "1_1") (pintype "passive"))
      (node (ref "U5") (pin "5") (pinfunction "EN_5") (pintype "bidirectional"))
      (node (ref "VE") (pin "2") (pinfunction "2_2") (pintype "passive"))
    )
    (net (code "46") (name "Net-(U5-IN)") (class "Default")
      (node (ref "5V_MEAS") (pin "2") (pinfunction "2_2") (pintype "passive"))
      (node (ref "5V_MEAS") (pin "4") (pinfunction "2_4") (pintype "passive"))
      (node (ref "C5") (pin "1") (pinfunction "1_1") (pintype "passive"))
      (node (ref "C8") (pin "1") (pinfunction "1_1") (pintype "passive"))
      (node (ref "R9") (pin "2") (pinfunction "2_2") (pintype "passive"))
      (node (ref "U5") (pin "8") (pinfunction "IN_8") (pintype "input"))
    )
    (net (code "47") (name "Net-(U5-OUT)") (class "Default")
      (node (ref "3V3_MEAS") (pin "1") (pinfunction "1_1") (pintype "passive"))
      (node (ref "3V3_MEAS") (pin "3") (pinfunction "1_3") (pintype "passive"))
      (node (ref "C11") (pin "1") (pinfunction "1_1") (pintype "passive"))
      (node (ref "C9") (pin "1") (pinfunction "1_1") (pintype "passive"))
      (node (ref "U5") (pin "1") (pinfunction "OUT_1") (pintype "output"))
    )
    (net (code "48") (name "PROCESSOR_CAN-RX") (class "Default")
      (node (ref "J1") (pin "41") (pinfunction "CAN-RX_41") (pintype "bidirectional"))
      (node (ref "J6") (pin "43") (pinfunction "CAN-TX_43") (pintype "bidirectional"))
    )
    (net (code "49") (name "PROCESSOR_CAN-TX") (class "Default")
      (node (ref "J1") (pin "43") (pinfunction "CAN-TX_43") (pintype "bidirectional"))
      (node (ref "J6") (pin "41") (pinfunction "CAN-RX_41") (pintype "bidirectional"))
    )
    (net (code "50") (name "PWM0-PROCESSOR") (class "Default")
      (node (ref "J1") (pin "32") (pinfunction "PWM0_32") (pintype "bidirectional"))
      (node (ref "J6") (pin "51") (pinfunction "F2/PWM_51") (pintype "bidirectional"))
    )
    (net (code "51") (name "PWR_EN0") (class "Default")
      (node (ref "J1") (pin "38") (pinfunction "A1_38") (pintype "bidirectional"))
      (node (ref "J6") (pin "71") (pinfunction "PWR_EN_71") (pintype "bidirectional"))
    )
    (net (code "52") (name "RTS1-PROCESSOR") (class "Default")
      (node (ref "J1") (pin "13") (pinfunction "RTS1_13") (pintype "bidirectional"))
      (node (ref "J6") (pin "18") (pinfunction "CTS_18") (pintype "bidirectional"))
    )
    (net (code "53") (name "RX1-DFU_TX-FC0-PLEX") (class "Default")
      (node (ref "J6") (pin "4") (pinfunction "DFU_FC_TX_4") (pintype "bidirectional"))
      (node (ref "U1") (pin "P9") (pinfunction "2S1_P9") (pintype "bidirectional"))
    )
    (net (code "54") (name "RX1-PROCESSOR") (class "Default")
      (node (ref "J1") (pin "19") (pinfunction "RX1_19") (pintype "bidirectional"))
      (node (ref "U1") (pin "P6") (pinfunction "D2_P6") (pintype "bidirectional"))
    )
    (net (code "55") (name "RX1-PROCESSOR-PLEX") (class "Default")
      (node (ref "J6") (pin "13") (pinfunction "TX_13") (pintype "bidirectional"))
      (node (ref "U1") (pin "P7") (pinfunction "2S3_P7") (pintype "bidirectional"))
    )
    (net (code "56") (name "RX1{slash}2S2") (class "Default")
      (node (ref "J7") (pin "2") (pinfunction "2_2") (pintype "passive"))
      (node (ref "U1") (pin "P8") (pinfunction "2S2_P8") (pintype "bidirectional"))
    )
    (net (code "57") (name "SPI_PROCESSOR_SCK") (class "Default")
      (node (ref "J1") (pin "57") (pinfunction "SPI_SCK_57") (pintype "bidirectional"))
      (node (ref "J10") (pin "5") (pinfunction "CLK/SCK_5") (pintype "bidirectional"))
      (node (ref "J6") (pin "3") (pinfunction "SPI_SCK_3") (pintype "bidirectional"))
    )
    (net (code "58") (name "SPI_PROCESSOR_SDI") (class "Default")
      (node (ref "J1") (pin "61") (pinfunction "SPI_SDI_61") (pintype "bidirectional"))
      (node (ref "J10") (pin "7") (pinfunction "DAT0/SDO_7") (pintype "bidirectional"))
      (node (ref "J6") (pin "7") (pinfunction "SPI_SDO_7") (pintype "bidirectional"))
    )
    (net (code "59") (name "SPI_PROCESSOR_SDO") (class "Default")
      (node (ref "J1") (pin "59") (pinfunction "SPI_SDO_59") (pintype "bidirectional"))
      (node (ref "J10") (pin "3") (pinfunction "CMD/SDI_3") (pintype "bidirectional"))
      (node (ref "J6") (pin "5") (pinfunction "SPI_SDI_5") (pintype "bidirectional"))
    )
    (net (code "60") (name "SWDCK") (class "Default")
      (node (ref "J1") (pin "21") (pinfunction "SWDCK_21") (pintype "bidirectional"))
      (node (ref "J5") (pin "4") (pinfunction "SWDCLK_4") (pintype "bidirectional"))
    )
    (net (code "61") (name "SWDIO") (class "Default")
      (node (ref "J1") (pin "23") (pinfunction "SWDIO_23") (pintype "bidirectional"))
      (node (ref "J5") (pin "2") (pinfunction "SWDIO_2") (pintype "bidirectional"))
      (node (ref "TP1") (pin "1") (pinfunction "1_1") (pintype "bidirectional"))
    )
    (net (code "62") (name "TX1-DFU_RX-FC0-PLEX") (class "Default")
      (node (ref "J6") (pin "6") (pinfunction "DFU_FC_RX_6") (pintype "bidirectional"))
      (node (ref "U1") (pin "P1") (pinfunction "1S1_P1") (pintype "bidirectional"))
    )
    (net (code "63") (name "TX1-PROCESSOR") (class "Default")
      (node (ref "J1") (pin "17") (pinfunction "TX1_17") (pintype "bidirectional"))
      (node (ref "U1") (pin "P4") (pinfunction "D1_P4") (pintype "bidirectional"))
    )
    (net (code "64") (name "TX1-PROCESSOR-PLEX") (class "Default")
      (node (ref "J6") (pin "15") (pinfunction "RX_15") (pintype "bidirectional"))
      (node (ref "U1") (pin "P3") (pinfunction "1S3_P3") (pintype "bidirectional"))
    )
    (net (code "65") (name "TX1{slash}1S2") (class "Default")
      (node (ref "J7") (pin "1") (pinfunction "1_1") (pintype "passive"))
      (node (ref "U1") (pin "P2") (pinfunction "1S2_P2") (pintype "bidirectional"))
    )
    (net (code "66") (name "VCC") (class "Default")
      (node (ref "5V_MEAS") (pin "1") (pinfunction "1_1") (pintype "passive"))
      (node (ref "5V_MEAS") (pin "3") (pinfunction "1_3") (pintype "passive"))
      (node (ref "C2") (pin "1") (pinfunction "1_1") (pintype "passive"))
      (node (ref "D5") (pin "C") (pinfunction "C_C") (pintype "passive"))
      (node (ref "J6") (pin "72") (pinfunction "VCC_72") (pintype "bidirectional"))
      (node (ref "J6") (pin "74") (pinfunction "VCC_74") (pintype "bidirectional"))
      (node (ref "Q1") (pin "2") (pinfunction "S_2") (pintype "bidirectional"))
      (node (ref "R4") (pin "2") (pinfunction "2_2") (pintype "passive"))
      (node (ref "U4") (pin "1") (pinfunction "IN_1") (pintype "input"))
    )
    (net (code "67") (name "VIN") (class "Default")
      (node (ref "BYP") (pin "2") (pinfunction "2_2") (pintype "passive"))
      (node (ref "C3") (pin "1") (pinfunction "1_1") (pintype "passive"))
      (node (ref "D5") (pin "A") (pinfunction "A_A") (pintype "passive"))
      (node (ref "F2") (pin "2") (pinfunction "2_2") (pintype "bidirectional"))
      (node (ref "J1") (pin "9") (pinfunction "USB_VIN_9") (pintype "bidirectional"))
      (node (ref "Q1") (pin "1") (pinfunction "G_1") (pintype "bidirectional"))
      (node (ref "R10") (pin "2") (pinfunction "2_2") (pintype "passive"))
      (node (ref "R5") (pin "1") (pinfunction "1_1") (pintype "passive"))
      (node (ref "R6") (pin "2") (pinfunction "2_2") (pintype "passive"))
      (node (ref "R8") (pin "2") (pinfunction "2_2") (pintype "passive"))
      (node (ref "TP4") (pin "1") (pinfunction "1_1") (pintype "bidirectional"))
      (node (ref "U2") (pin "4") (pinfunction "VIN_4") (pintype "power_in"))
    )
    (net (code "68") (name "VIN{slash}3") (class "Default")
      (node (ref "J1") (pin "49") (pinfunction "BATT_VIN/3_49") (pintype "bidirectional"))
      (node (ref "R10") (pin "1") (pinfunction "1_1") (pintype "passive"))
      (node (ref "R7") (pin "2") (pinfunction "2_2") (pintype "passive"))
    )
    (net (code "69") (name "V_BATT") (class "Default")
      (node (ref "C4") (pin "1") (pinfunction "1_1") (pintype "passive"))
      (node (ref "J12") (pin "2") (pinfunction "2_2") (pintype "passive"))
      (node (ref "J8") (pin "2") (pinfunction "+_2") (pintype "bidirectional"))
      (node (ref "Q1") (pin "3") (pinfunction "D_3") (pintype "bidirectional"))
      (node (ref "TP3") (pin "1") (pinfunction "1_1") (pintype "bidirectional"))
      (node (ref "U2") (pin "3") (pinfunction "VBAT_3") (pintype "power_in"))
    )
    (net (code "70") (name "V_USB") (class "Default")
      (node (ref "BYP") (pin "1") (pinfunction "1_1") (pintype "passive"))
      (node (ref "F2") (pin "1") (pinfunction "1_1") (pintype "bidirectional"))
      (node (ref "J3") (pin "VBUS1") (pinfunction "VBUS_VBUS1") (pintype "bidirectional"))
      (node (ref "J3") (pin "VBUS2") (pinfunction "VBUS_VBUS2") (pintype "bidirectional"))
      (node (ref "U3") (pin "5") (pinfunction "VCC_5") (pintype "bidirectional"))
    )
    (net (code "71") (name "unconnected-(J1-AUD_BCLK-Pad50)") (class "Default")
      (node (ref "J1") (pin "50") (pinfunction "AUD_BCLK_50") (pintype "bidirectional"))
    )
    (net (code "72") (name "unconnected-(J1-AUD_IN{slash}CAM_PCLK-Pad54)") (class "Default")
      (node (ref "J1") (pin "54") (pinfunction "AUD_IN/CAM_PCLK_54") (pintype "bidirectional"))
    )
    (net (code "73") (name "unconnected-(J1-AUD_LRCLK-Pad52)") (class "Default")
      (node (ref "J1") (pin "52") (pinfunction "AUD_LRCLK_52") (pintype "bidirectional"))
    )
    (net (code "74") (name "unconnected-(J1-AUD_MCLK-Pad58)") (class "Default")
      (node (ref "J1") (pin "58") (pinfunction "AUD_MCLK_58") (pintype "bidirectional"))
    )
    (net (code "75") (name "unconnected-(J1-AUD_OUT{slash}CAM_MCLK-Pad56)") (class "Default")
      (node (ref "J1") (pin "56") (pinfunction "AUD_OUT/CAM_MCLK_56") (pintype "bidirectional"))
    )
    (net (code "76") (name "unconnected-(J1-G5{slash}BUS5-Pad73)") (class "Default")
      (node (ref "J1") (pin "73") (pinfunction "G5/BUS5_73") (pintype "bidirectional"))
    )
    (net (code "77") (name "unconnected-(J1-G6{slash}BUS6-Pad71)") (class "Default")
      (node (ref "J1") (pin "71") (pinfunction "G6/BUS6_71") (pintype "bidirectional"))
    )
    (net (code "78") (name "unconnected-(J1-G7{slash}BUS7-Pad69)") (class "Default")
      (node (ref "J1") (pin "69") (pinfunction "G7/BUS7_69") (pintype "bidirectional"))
    )
    (net (code "79") (name "unconnected-(J1-G8-Pad67)") (class "Default")
      (node (ref "J1") (pin "67") (pinfunction "G8_67") (pintype "bidirectional"))
    )
    (net (code "80") (name "unconnected-(J1-G9{slash}ADC_D-{slash}CAM_HSYNC-Pad65)") (class "Default")
      (node (ref "J1") (pin "65") (pinfunction "G9/ADC_D-/CAM_HSYNC_65") (pintype "bidirectional"))
    )
    (net (code "81") (name "unconnected-(J1-G10{slash}ADC_D+{slash}CAM_VSYNC-Pad63)") (class "Default")
      (node (ref "J1") (pin "63") (pinfunction "G10/ADC_D+/CAM_VSYNC_63") (pintype "bidirectional"))
    )
    (net (code "82") (name "unconnected-(J1-G11-Pad8)") (class "Default")
      (node (ref "J1") (pin "8") (pinfunction "G11_8") (pintype "bidirectional"))
    )
    (net (code "83") (name "unconnected-(J1-PWM1-Pad47)") (class "Default")
      (node (ref "J1") (pin "47") (pinfunction "PWM1_47") (pintype "bidirectional"))
    )
    (net (code "84") (name "unconnected-(J1-RTC_3V-Pad72)") (class "Default")
      (node (ref "J1") (pin "72") (pinfunction "RTC_3V_72") (pintype "bidirectional"))
    )
    (net (code "85") (name "unconnected-(J1-RX2-Pad20)") (class "Default")
      (node (ref "J1") (pin "20") (pinfunction "RX2_20") (pintype "bidirectional"))
    )
    (net (code "86") (name "unconnected-(J1-SDIO_DATA1-Pad66)") (class "Default")
      (node (ref "J1") (pin "66") (pinfunction "SDIO_DATA1_66") (pintype "bidirectional"))
    )
    (net (code "87") (name "unconnected-(J1-SDIO_DATA2-Pad68)") (class "Default")
      (node (ref "J1") (pin "68") (pinfunction "SDIO_DATA2_68") (pintype "bidirectional"))
    )
    (net (code "88") (name "unconnected-(J1-SPI_SCK1{slash}SDIO_CLK-Pad60)") (class "Default")
      (node (ref "J1") (pin "60") (pinfunction "SPI_SCK1/SDIO_CLK_60") (pintype "bidirectional"))
    )
    (net (code "89") (name "unconnected-(J1-SPI_SDI1{slash}SDIO_DATA0-Pad64)") (class "Default")
      (node (ref "J1") (pin "64") (pinfunction "SPI_SDI1/SDIO_DATA0_64") (pintype "bidirectional"))
    )
    (net (code "90") (name "unconnected-(J1-SPI_SDO1{slash}SDIO_CMD-Pad62)") (class "Default")
      (node (ref "J1") (pin "62") (pinfunction "SPI_SDO1/SDIO_CMD_62") (pintype "bidirectional"))
    )
    (net (code "91") (name "unconnected-(J1-SPI_~{CS1}{slash}SDIO_DATA3-Pad70)") (class "Default")
      (node (ref "J1") (pin "70") (pinfunction "SPI_~{CS1}/SDIO_DATA3_70") (pintype "bidirectional"))
    )
    (net (code "92") (name "unconnected-(J1-TX2-Pad22)") (class "Default")
      (node (ref "J1") (pin "22") (pinfunction "TX2_22") (pintype "bidirectional"))
    )
    (net (code "93") (name "unconnected-(J5-SWO-Pad6)") (class "Default")
      (node (ref "J5") (pin "6") (pinfunction "SWO_6") (pintype "bidirectional"))
    )
    (net (code "94") (name "unconnected-(J6-EEPROM_WP-Pad40)") (class "Default")
      (node (ref "J6") (pin "40") (pinfunction "EEPROM_WP_40") (pintype "bidirectional"))
    )
    (net (code "95") (name "unconnected-(J6-USB_VIN-Pad70)") (class "Default")
      (node (ref "J6") (pin "70") (pinfunction "USB_VIN_70") (pintype "bidirectional"))
    )
    (net (code "96") (name "unconnected-(J8-PAD1-PadNC1)") (class "Default")
      (node (ref "J8") (pin "NC1") (pinfunction "PAD1_NC1") (pintype "bidirectional"))
    )
    (net (code "97") (name "unconnected-(J8-PAD2-PadNC2)") (class "Default")
      (node (ref "J8") (pin "NC2") (pinfunction "PAD2_NC2") (pintype "bidirectional"))
    )
    (net (code "98") (name "unconnected-(J10-DAT1-Pad8)") (class "Default")
      (node (ref "J10") (pin "8") (pinfunction "DAT1_8") (pintype "bidirectional"))
    )
    (net (code "99") (name "unconnected-(J10-DAT2-Pad1)") (class "Default")
      (node (ref "J10") (pin "1") (pinfunction "DAT2_1") (pintype "bidirectional"))
    )
    (net (code "100") (name "unconnected-(J10-DET-Pad9)") (class "Default")
      (node (ref "J10") (pin "9") (pinfunction "DET_9") (pintype "bidirectional"))
    )
    (net (code "101") (name "unconnected-(U3-IO1-Pad1)") (class "Default")
      (node (ref "U3") (pin "1") (pinfunction "IO1_1") (pintype "bidirectional"))
    )
    (net (code "102") (name "unconnected-(U3-IO2-Pad3)") (class "Default")
      (node (ref "U3") (pin "3") (pinfunction "IO2_3") (pintype "bidirectional"))
    )
  )
)
